# 2_main.net
KiCad netlist of a schematic drawn in EAGLE
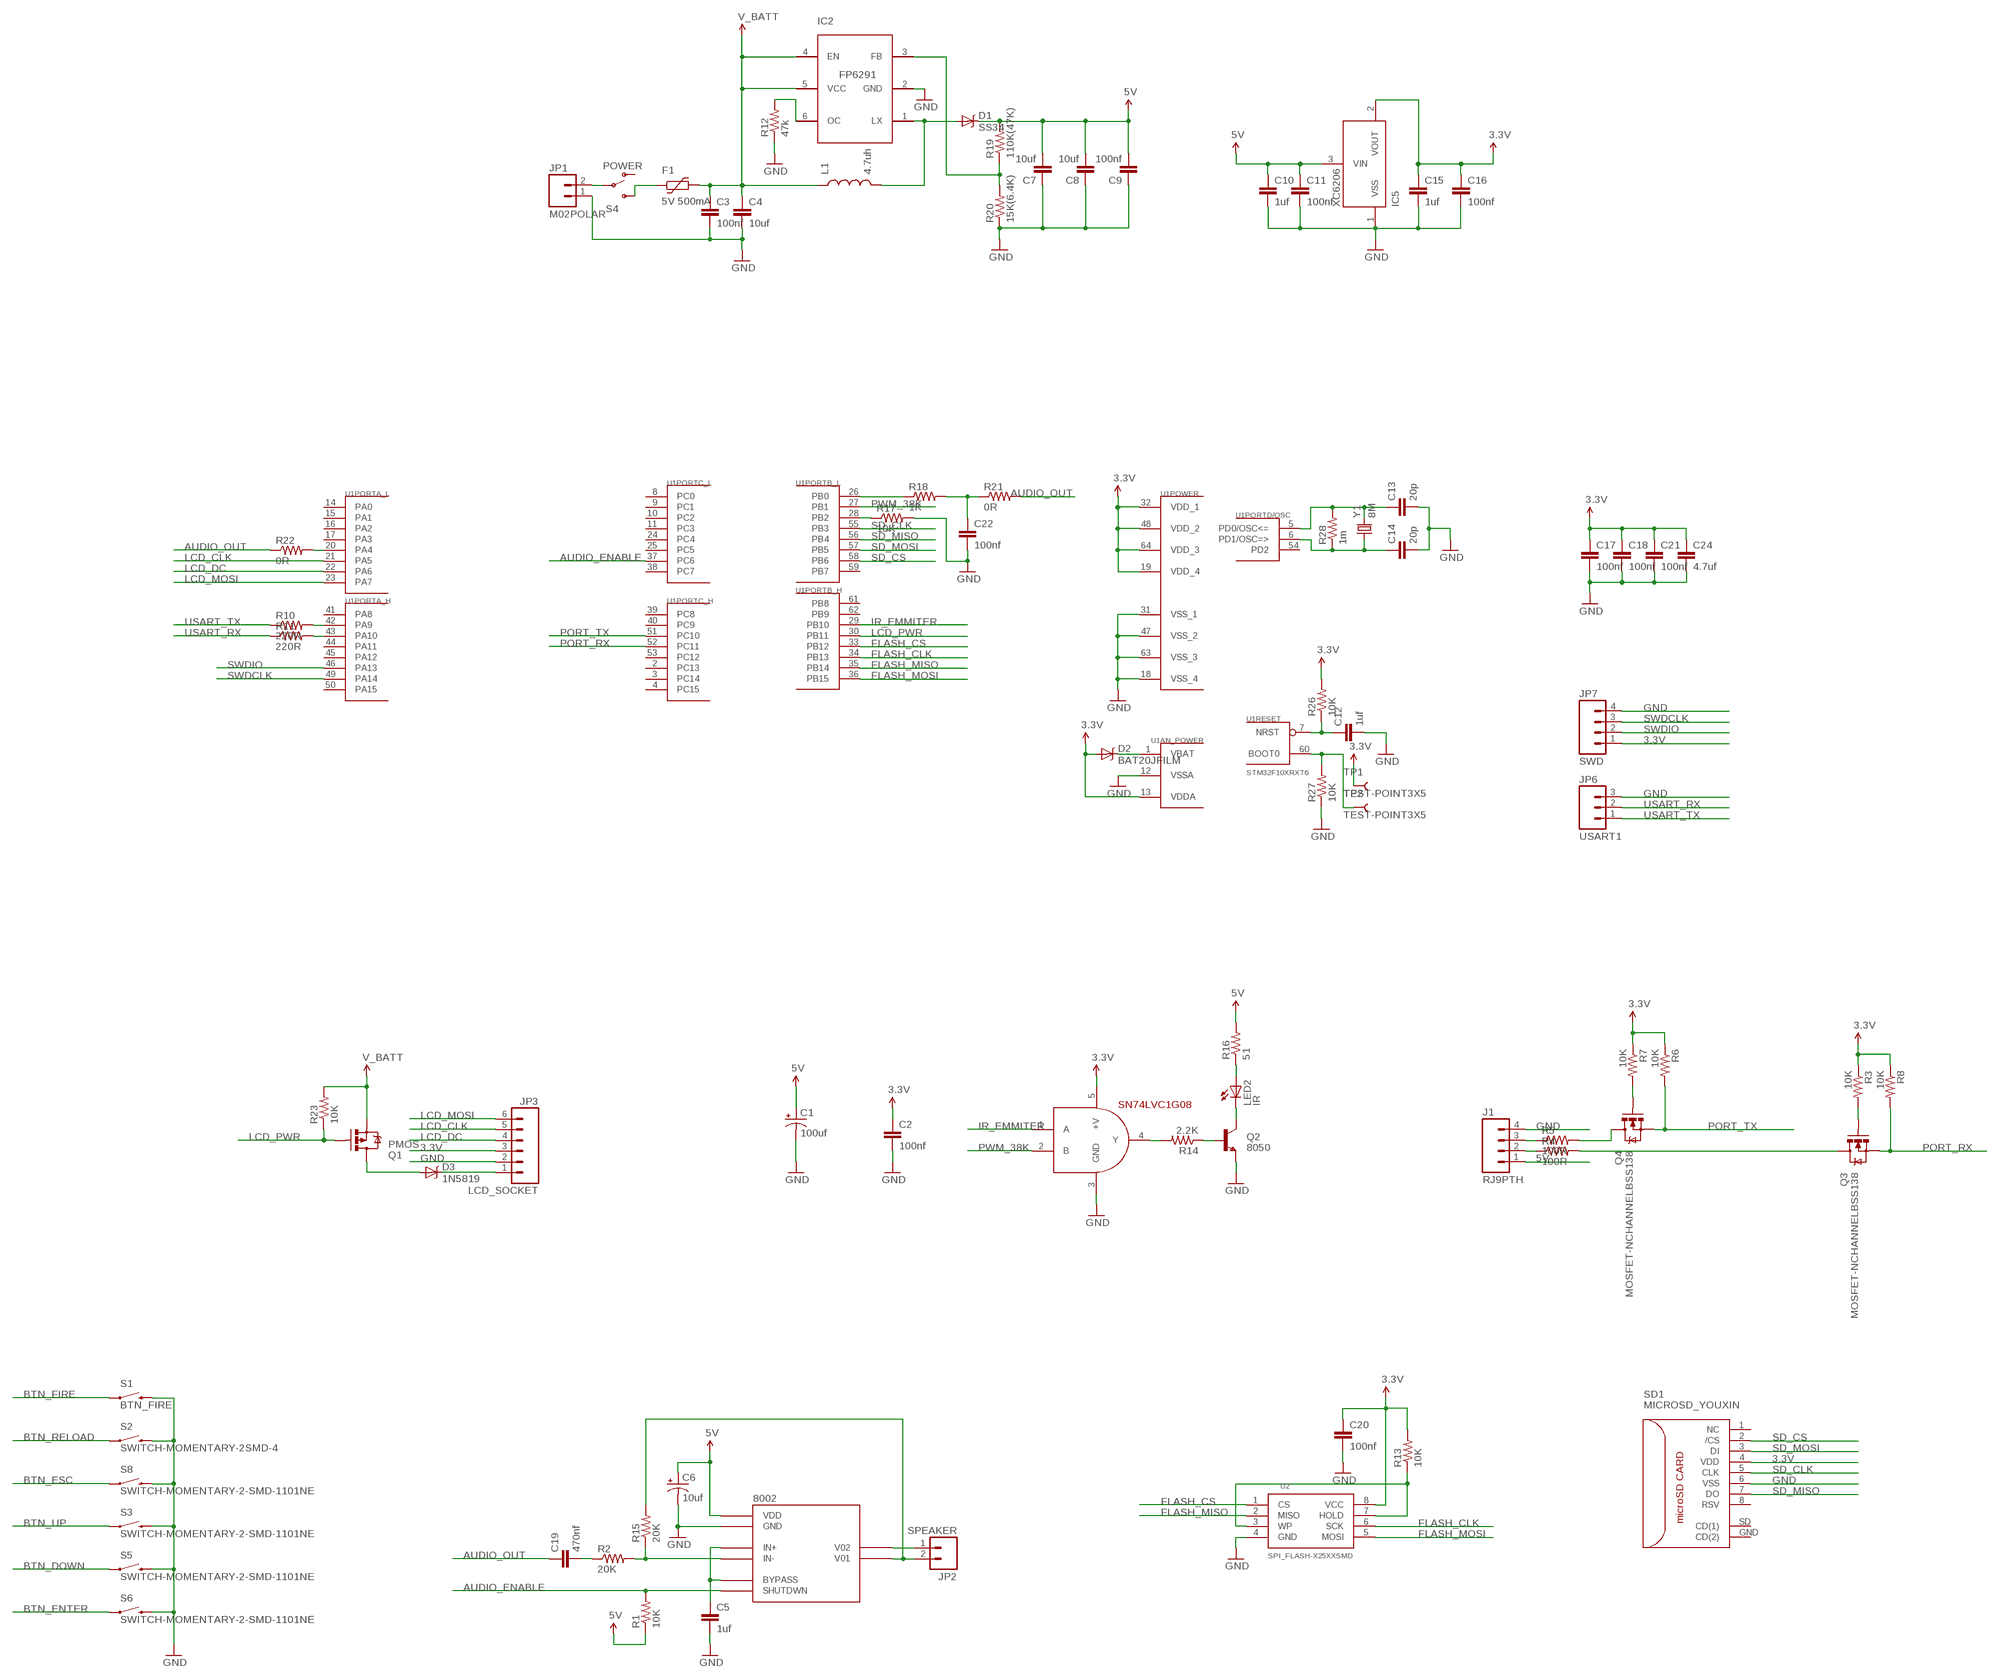
[diagram p0: schematic, sheet 1]

(export (version "E")
  (design (tool "Eeschema 10.0.6"))
  (components
    (comp (ref "8002")
      (value "LM4871")
      (footprint "eagle-import:SO08")
      (libsource (lib "eagle-import") (part "LM4871"))
    )
    (comp (ref "C1")
      (value "100uf")
      (footprint "eagle-import:EIA6032")
      (libsource (lib "eagle-import") (part "CAP_POL6032"))
    )
    (comp (ref "C2")
      (value "100nf")
      (footprint "eagle-import:0603-CAP")
      (libsource (lib "eagle-import") (part "CAP0603-CAP"))
    )
    (comp (ref "C3")
      (value "100nf")
      (footprint "eagle-import:0603-CAP")
      (libsource (lib "eagle-import") (part "CAP0603-CAP"))
    )
    (comp (ref "C4")
      (value "10uf")
      (footprint "eagle-import:0603-CAP")
      (libsource (lib "eagle-import") (part "CAP0603-CAP"))
    )
    (comp (ref "C5")
      (value "1uf")
      (footprint "eagle-import:0603-CAP")
      (libsource (lib "eagle-import") (part "CAP0603-CAP"))
    )
    (comp (ref "C6")
      (value "10uf")
      (footprint "eagle-import:EIA3216-KIT")
      (libsource (lib "eagle-import") (part "CAP_POL1206-KIT"))
    )
    (comp (ref "C7")
      (value "10uf")
      (footprint "eagle-import:0603-CAP")
      (libsource (lib "eagle-import") (part "CAP0603-CAP"))
    )
    (comp (ref "C8")
      (value "10uf")
      (footprint "eagle-import:0603-CAP")
      (libsource (lib "eagle-import") (part "CAP0603-CAP"))
    )
    (comp (ref "C9")
      (value "100nf")
      (footprint "eagle-import:0603-CAP")
      (libsource (lib "eagle-import") (part "CAP0603-CAP"))
    )
    (comp (ref "C10")
      (value "1uf")
      (footprint "eagle-import:0603-CAP")
      (libsource (lib "eagle-import") (part "CAP0603-CAP"))
    )
    (comp (ref "C11")
      (value "100nf")
      (footprint "eagle-import:0603-CAP")
      (libsource (lib "eagle-import") (part "CAP0603-CAP"))
    )
    (comp (ref "C12")
      (value "1uf")
      (footprint "eagle-import:0603-CAP")
      (libsource (lib "eagle-import") (part "CAP0603-CAP"))
    )
    (comp (ref "C13")
      (value "20p")
      (footprint "eagle-import:0603-CAP")
      (libsource (lib "eagle-import") (part "CAP0603-CAP"))
    )
    (comp (ref "C14")
      (value "20p")
      (footprint "eagle-import:0603-CAP")
      (libsource (lib "eagle-import") (part "CAP0603-CAP"))
    )
    (comp (ref "C15")
      (value "1uf")
      (footprint "eagle-import:0603-CAP")
      (libsource (lib "eagle-import") (part "CAP0603-CAP"))
    )
    (comp (ref "C16")
      (value "100nf")
      (footprint "eagle-import:0603-CAP")
      (libsource (lib "eagle-import") (part "CAP0603-CAP"))
    )
    (comp (ref "C17")
      (value "100nf")
      (footprint "eagle-import:0603-CAP")
      (libsource (lib "eagle-import") (part "CAP0603-CAP"))
    )
    (comp (ref "C18")
      (value "100nf")
      (footprint "eagle-import:0603-CAP")
      (libsource (lib "eagle-import") (part "CAP0603-CAP"))
    )
    (comp (ref "C19")
      (value "470nf")
      (footprint "eagle-import:0603-CAP")
      (libsource (lib "eagle-import") (part "CAP0603-CAP"))
    )
    (comp (ref "C20")
      (value "100nf")
      (footprint "eagle-import:0603-CAP")
      (libsource (lib "eagle-import") (part "CAP0603-CAP"))
    )
    (comp (ref "C21")
      (value "100nf")
      (footprint "eagle-import:0603-CAP")
      (libsource (lib "eagle-import") (part "CAP0603-CAP"))
    )
    (comp (ref "C22")
      (value "100nf")
      (footprint "eagle-import:0603-CAP")
      (libsource (lib "eagle-import") (part "CAP0603-CAP"))
    )
    (comp (ref "C24")
      (value "4.7uf")
      (footprint "eagle-import:0603-CAP")
      (libsource (lib "eagle-import") (part "CAP0603-CAP"))
    )
    (comp (ref "D1")
      (value "SS34")
      (footprint "eagle-import:SMA-DIODE")
      (libsource (lib "eagle-import") (part "DIODE-SCHOTTKY_"))
    )
    (comp (ref "D2")
      (value "BAT20JFILM")
      (footprint "eagle-import:SOD-323")
      (libsource (lib "eagle-import") (part "BAT20JFILM"))
    )
    (comp (ref "D3")
      (value "1N5819")
      (footprint "eagle-import:SOD-323")
      (libsource (lib "eagle-import") (part "BAT20JFILM"))
    )
    (comp (ref "F1")
      (value "5V 500mA")
      (footprint "eagle-import:R0805")
      (libsource (lib "eagle-import") (part "PTC-FUSE"))
    )
    (comp (ref "IC1")
      (value "SN74LVC1G08")
      (footprint "eagle-import:SOT23-5")
      (libsource (lib "eagle-import") (part "SN74LVC1G08"))
    )
    (comp (ref "IC2")
      (value "FP6291")
      (footprint "eagle-import:SOT23-6")
      (libsource (lib "eagle-import") (part "FP6291"))
    )
    (comp (ref "IC5")
      (value "XC6206")
      (footprint "eagle-import:SOT23-3")
      (libsource (lib "eagle-import") (part "XC6206"))
    )
    (comp (ref "J1")
      (value "RJ9PTH")
      (footprint "eagle-import:RJ9")
      (libsource (lib "eagle-import") (part "RJ9PTH"))
    )
    (comp (ref "JP1")
      (value "M02POLAR")
      (footprint "eagle-import:MOLEX-1X2")
      (libsource (lib "eagle-import") (part "M02POLAR"))
    )
    (comp (ref "JP2")
      (value "SPEAKER")
      (footprint "eagle-import:MOLEX-1X2")
      (libsource (lib "eagle-import") (part "M02POLAR"))
    )
    (comp (ref "JP3")
      (value "LCD_SOCKET")
      (footprint "eagle-import:MOLEX-1X6")
      (libsource (lib "eagle-import") (part "M06POLAR"))
    )
    (comp (ref "JP6")
      (value "USART1")
      (footprint "eagle-import:1X03")
      (libsource (lib "eagle-import") (part "M03PTH"))
    )
    (comp (ref "JP7")
      (value "SWD")
      (footprint "eagle-import:1X04")
      (libsource (lib "eagle-import") (part "M04PTH"))
    )
    (comp (ref "L1")
      (value "4.7uh")
      (footprint "eagle-import:CR75_V2")
      (libsource (lib "eagle-import") (part "INDUCTORCR75_V2"))
    )
    (comp (ref "LED2")
      (value "IR")
      (footprint "eagle-import:LED5MM")
      (libsource (lib "eagle-import") (part "LED5MM"))
    )
    (comp (ref "Q1")
      (value "PMOS")
      (footprint "eagle-import:SOT23-3")
      (libsource (lib "eagle-import") (part "MOSFET-PCHANNELSMD"))
    )
    (comp (ref "Q2")
      (value "8050")
      (footprint "eagle-import:SOT23")
      (libsource (lib "eagle-import") (part "TRANSISTOR_NPNSOT23"))
    )
    (comp (ref "Q3")
      (value "MOSFET-NCHANNELBSS138")
      (footprint "eagle-import:SOT23")
      (libsource (lib "eagle-import") (part "MOSFET-NCHANNELBSS138"))
    )
    (comp (ref "Q4")
      (value "MOSFET-NCHANNELBSS138")
      (footprint "eagle-import:SOT23")
      (libsource (lib "eagle-import") (part "MOSFET-NCHANNELBSS138"))
    )
    (comp (ref "R1")
      (value "10K")
      (footprint "eagle-import:0603-RES")
      (libsource (lib "eagle-import") (part "RESISTOR0603-RES"))
    )
    (comp (ref "R2")
      (value "20K")
      (footprint "eagle-import:0603-RES")
      (libsource (lib "eagle-import") (part "RESISTOR0603-RES"))
    )
    (comp (ref "R3")
      (value "10K")
      (footprint "eagle-import:0603-RES")
      (libsource (lib "eagle-import") (part "RESISTOR0603-RES"))
    )
    (comp (ref "R4")
      (value "100R")
      (footprint "eagle-import:0603-RES")
      (libsource (lib "eagle-import") (part "RESISTOR0603-RES"))
    )
    (comp (ref "R5")
      (value "100R")
      (footprint "eagle-import:0603-RES")
      (libsource (lib "eagle-import") (part "RESISTOR0603-RES"))
    )
    (comp (ref "R6")
      (value "10K")
      (footprint "eagle-import:0603-RES")
      (libsource (lib "eagle-import") (part "RESISTOR0603-RES"))
    )
    (comp (ref "R7")
      (value "10K")
      (footprint "eagle-import:0603-RES")
      (libsource (lib "eagle-import") (part "RESISTOR0603-RES"))
    )
    (comp (ref "R8")
      (value "10K")
      (footprint "eagle-import:0603-RES")
      (libsource (lib "eagle-import") (part "RESISTOR0603-RES"))
    )
    (comp (ref "R10")
      (value "220R")
      (footprint "eagle-import:0603-RES")
      (libsource (lib "eagle-import") (part "RESISTOR0603-RES"))
    )
    (comp (ref "R11")
      (value "220R")
      (footprint "eagle-import:0603-RES")
      (libsource (lib "eagle-import") (part "RESISTOR0603-RES"))
    )
    (comp (ref "R12")
      (value "47k")
      (footprint "eagle-import:0603-RES")
      (libsource (lib "eagle-import") (part "RESISTOR0603-RES"))
    )
    (comp (ref "R13")
      (value "10K")
      (footprint "eagle-import:0603-RES")
      (libsource (lib "eagle-import") (part "RESISTOR0603-RES"))
    )
    (comp (ref "R14")
      (value "2.2K")
      (footprint "eagle-import:0603-RES")
      (libsource (lib "eagle-import") (part "RESISTOR0603-RES"))
    )
    (comp (ref "R15")
      (value "20K")
      (footprint "eagle-import:0603-RES")
      (libsource (lib "eagle-import") (part "RESISTOR0603-RES"))
    )
    (comp (ref "R16")
      (value "51")
      (footprint "eagle-import:0603-RES")
      (libsource (lib "eagle-import") (part "RESISTOR0603-RES"))
    )
    (comp (ref "R17")
      (value "10K")
      (footprint "eagle-import:0603-RES")
      (libsource (lib "eagle-import") (part "RESISTOR0603-RES"))
    )
    (comp (ref "R18")
      (value "1K")
      (footprint "eagle-import:0603-RES")
      (libsource (lib "eagle-import") (part "RESISTOR0603-RES"))
    )
    (comp (ref "R19")
      (value "110K(47K)")
      (footprint "eagle-import:0603-RES")
      (libsource (lib "eagle-import") (part "RESISTOR0603-RES"))
    )
    (comp (ref "R20")
      (value "15K(6.4K)")
      (footprint "eagle-import:0603-RES")
      (libsource (lib "eagle-import") (part "RESISTOR0603-RES"))
    )
    (comp (ref "R21")
      (value "0R")
      (footprint "eagle-import:0603-RES")
      (libsource (lib "eagle-import") (part "RESISTOR0603-RES"))
    )
    (comp (ref "R22")
      (value "0R")
      (footprint "eagle-import:0603-RES")
      (libsource (lib "eagle-import") (part "RESISTOR0603-RES"))
    )
    (comp (ref "R23")
      (value "10K")
      (footprint "eagle-import:0603-RES")
      (libsource (lib "eagle-import") (part "RESISTOR0603-RES"))
    )
    (comp (ref "R26")
      (value "10K")
      (footprint "eagle-import:0603-RES")
      (libsource (lib "eagle-import") (part "RESISTOR0603-RES"))
    )
    (comp (ref "R27")
      (value "10K")
      (footprint "eagle-import:0603-RES")
      (libsource (lib "eagle-import") (part "RESISTOR0603-RES"))
    )
    (comp (ref "R28")
      (value "1m")
      (footprint "eagle-import:0603-RES")
      (libsource (lib "eagle-import") (part "RESISTOR0603-RES"))
    )
    (comp (ref "S1")
      (value "BTN_FIRE")
      (footprint "eagle-import:TACTILE_SWITCH_TALL")
      (libsource (lib "eagle-import") (part "SWITCH-MOMENTARY-2SMD-4"))
    )
    (comp (ref "S2")
      (value "SWITCH-MOMENTARY-2SMD-4")
      (footprint "eagle-import:TACTILE_SWITCH_TALL")
      (libsource (lib "eagle-import") (part "SWITCH-MOMENTARY-2SMD-4"))
    )
    (comp (ref "S3")
      (value "SWITCH-MOMENTARY-2-SMD-1101NE")
      (footprint "eagle-import:TACTILE-SWITCH-1101NE")
      (libsource (lib "eagle-import") (part "SWITCH-MOMENTARY-2-SMD-1101NE"))
    )
    (comp (ref "S4")
      (value "POWER")
      (footprint "eagle-import:SWITCH-SPDT-AM#6")
      (libsource (lib "eagle-import") (part "SWITCH-SPST3AM6"))
    )
    (comp (ref "S5")
      (value "SWITCH-MOMENTARY-2-SMD-1101NE")
      (footprint "eagle-import:TACTILE-SWITCH-1101NE")
      (libsource (lib "eagle-import") (part "SWITCH-MOMENTARY-2-SMD-1101NE"))
    )
    (comp (ref "S6")
      (value "SWITCH-MOMENTARY-2-SMD-1101NE")
      (footprint "eagle-import:TACTILE-SWITCH-1101NE")
      (libsource (lib "eagle-import") (part "SWITCH-MOMENTARY-2-SMD-1101NE"))
    )
    (comp (ref "S8")
      (value "SWITCH-MOMENTARY-2-SMD-1101NE")
      (footprint "eagle-import:TACTILE-SWITCH-1101NE")
      (libsource (lib "eagle-import") (part "SWITCH-MOMENTARY-2-SMD-1101NE"))
    )
    (comp (ref "SD1")
      (value "MICROSD_YOUXIN")
      (footprint "eagle-import:MICRO_SD_YOUXIN")
      (libsource (lib "eagle-import") (part "MICROSD_YOUXIN"))
    )
    (comp (ref "TP1")
      (value "TEST-POINT3X5")
      (footprint "eagle-import:PAD.03X.05")
      (libsource (lib "eagle-import") (part "TEST-POINT3X5"))
    )
    (comp (ref "TP2")
      (value "TEST-POINT3X5")
      (footprint "eagle-import:PAD.03X.05")
      (libsource (lib "eagle-import") (part "TEST-POINT3X5"))
    )
    (comp (ref "U1")
      (value "STM32F10XRXT6")
      (footprint "eagle-import:TQFP64")
      (libsource (lib "eagle-import") (part "STM32F10XRXT6"))
    )
    (comp (ref "U2")
      (value "SPI_FLASH-X25XXSMD")
      (footprint "eagle-import:SO08")
      (libsource (lib "eagle-import") (part "SPI_FLASH-X25XXSMD"))
    )
    (comp (ref "Y1")
      (value "8M")
      (footprint "eagle-import:CRYSTAL-TXC-7A")
      (libsource (lib "eagle-import") (part "CRYSTALTXC-7A"))
    )
  )
  (nets
    (net (code "1") (name "/AUDIO_ENABLE") (class "Default")
      (node (ref "8002") (pin "1") (pinfunction "SHUTDWN_1") (pintype "bidirectional"))
      (node (ref "R1") (pin "2") (pinfunction "2_2") (pintype "passive"))
      (node (ref "U1") (pin "37") (pinfunction "PC6_37") (pintype "bidirectional"))
    )
    (net (code "2") (name "/AUDIO_OUT") (class "Default")
      (node (ref "C19") (pin "1") (pinfunction "1_1") (pintype "passive"))
      (node (ref "R21") (pin "2") (pinfunction "2_2") (pintype "passive"))
      (node (ref "R22") (pin "1") (pinfunction "1_1") (pintype "passive"))
    )
    (net (code "3") (name "/BTN_DOWN") (class "Default")
      (node (ref "S5") (pin "P$1") (pinfunction "1_P$1") (pintype "passive"))
    )
    (net (code "4") (name "/BTN_ENTER") (class "Default")
      (node (ref "S6") (pin "P$1") (pinfunction "1_P$1") (pintype "passive"))
    )
    (net (code "5") (name "/BTN_ESC") (class "Default")
      (node (ref "S8") (pin "P$1") (pinfunction "1_P$1") (pintype "passive"))
    )
    (net (code "6") (name "/BTN_FIRE") (class "Default")
      (node (ref "S1") (pin "A2") (pinfunction "1_A2") (pintype "passive"))
    )
    (net (code "7") (name "/BTN_RELOAD") (class "Default")
      (node (ref "S2") (pin "A2") (pinfunction "1_A2") (pintype "passive"))
    )
    (net (code "8") (name "/BTN_UP") (class "Default")
      (node (ref "S3") (pin "P$1") (pinfunction "1_P$1") (pintype "passive"))
    )
    (net (code "9") (name "/FLASH_CLK") (class "Default")
      (node (ref "U1") (pin "34") (pinfunction "PB13_34") (pintype "bidirectional"))
      (node (ref "U2") (pin "6") (pinfunction "SCK_6") (pintype "bidirectional"))
    )
    (net (code "10") (name "/FLASH_CS") (class "Default")
      (node (ref "U1") (pin "33") (pinfunction "PB12_33") (pintype "bidirectional"))
      (node (ref "U2") (pin "1") (pinfunction "CS_1") (pintype "bidirectional"))
    )
    (net (code "11") (name "/FLASH_MISO") (class "Default")
      (node (ref "U1") (pin "35") (pinfunction "PB14_35") (pintype "bidirectional"))
      (node (ref "U2") (pin "2") (pinfunction "MISO_2") (pintype "bidirectional"))
    )
    (net (code "12") (name "/FLASH_MOSI") (class "Default")
      (node (ref "U1") (pin "36") (pinfunction "PB15_36") (pintype "bidirectional"))
      (node (ref "U2") (pin "5") (pinfunction "MOSI_5") (pintype "bidirectional"))
    )
    (net (code "13") (name "/IR_EMMITER") (class "Default")
      (node (ref "IC1") (pin "1") (pinfunction "A_1") (pintype "bidirectional"))
      (node (ref "U1") (pin "29") (pinfunction "PB10_29") (pintype "bidirectional"))
    )
    (net (code "14") (name "/LCD_CLK") (class "Default")
      (node (ref "JP3") (pin "5") (pinfunction "5_5") (pintype "passive"))
      (node (ref "U1") (pin "21") (pinfunction "PA5_21") (pintype "bidirectional"))
    )
    (net (code "15") (name "/LCD_DC") (class "Default")
      (node (ref "JP3") (pin "4") (pinfunction "4_4") (pintype "passive"))
      (node (ref "U1") (pin "22") (pinfunction "PA6_22") (pintype "bidirectional"))
    )
    (net (code "16") (name "/LCD_MOSI") (class "Default")
      (node (ref "JP3") (pin "6") (pinfunction "6_6") (pintype "passive"))
      (node (ref "U1") (pin "23") (pinfunction "PA7_23") (pintype "bidirectional"))
    )
    (net (code "17") (name "/LCD_PWR") (class "Default")
      (node (ref "Q1") (pin "1") (pinfunction "G_1") (pintype "passive"))
      (node (ref "R23") (pin "1") (pinfunction "1_1") (pintype "passive"))
      (node (ref "U1") (pin "30") (pinfunction "PB11_30") (pintype "bidirectional"))
    )
    (net (code "18") (name "/PORT_RX") (class "Default")
      (node (ref "Q3") (pin "2") (pinfunction "S_2") (pintype "passive"))
      (node (ref "R8") (pin "2") (pinfunction "2_2") (pintype "passive"))
      (node (ref "U1") (pin "52") (pinfunction "PC11_52") (pintype "bidirectional"))
    )
    (net (code "19") (name "/PORT_TX") (class "Default")
      (node (ref "Q4") (pin "2") (pinfunction "S_2") (pintype "passive"))
      (node (ref "R6") (pin "2") (pinfunction "2_2") (pintype "passive"))
      (node (ref "U1") (pin "51") (pinfunction "PC10_51") (pintype "bidirectional"))
    )
    (net (code "20") (name "/PWM_38K") (class "Default")
      (node (ref "IC1") (pin "2") (pinfunction "B_2") (pintype "bidirectional"))
      (node (ref "U1") (pin "27") (pinfunction "PB1_27") (pintype "bidirectional"))
    )
    (net (code "21") (name "/SD_CLK") (class "Default")
      (node (ref "SD1") (pin "5") (pinfunction "CLK_5") (pintype "bidirectional"))
      (node (ref "U1") (pin "55") (pinfunction "PB3_55") (pintype "bidirectional"))
    )
    (net (code "22") (name "/SD_CS") (class "Default")
      (node (ref "SD1") (pin "2") (pinfunction "/CS_2") (pintype "bidirectional"))
      (node (ref "U1") (pin "58") (pinfunction "PB6_58") (pintype "bidirectional"))
    )
    (net (code "23") (name "/SD_MISO") (class "Default")
      (node (ref "SD1") (pin "7") (pinfunction "DO_7") (pintype "bidirectional"))
      (node (ref "U1") (pin "56") (pinfunction "PB4_56") (pintype "bidirectional"))
    )
    (net (code "24") (name "/SD_MOSI") (class "Default")
      (node (ref "SD1") (pin "3") (pinfunction "DI_3") (pintype "bidirectional"))
      (node (ref "U1") (pin "57") (pinfunction "PB5_57") (pintype "bidirectional"))
    )
    (net (code "25") (name "/SWDCLK") (class "Default")
      (node (ref "JP7") (pin "3") (pinfunction "3_3") (pintype "passive"))
      (node (ref "U1") (pin "49") (pinfunction "PA14_49") (pintype "bidirectional"))
    )
    (net (code "26") (name "/SWDIO") (class "Default")
      (node (ref "JP7") (pin "2") (pinfunction "2_2") (pintype "passive"))
      (node (ref "U1") (pin "46") (pinfunction "PA13_46") (pintype "bidirectional"))
    )
    (net (code "27") (name "/USART_RX") (class "Default")
      (node (ref "JP6") (pin "2") (pinfunction "2_2") (pintype "passive"))
      (node (ref "R11") (pin "1") (pinfunction "1_1") (pintype "passive"))
    )
    (net (code "28") (name "/USART_TX") (class "Default")
      (node (ref "JP6") (pin "1") (pinfunction "1_1") (pintype "passive"))
      (node (ref "R10") (pin "1") (pinfunction "1_1") (pintype "passive"))
    )
    (net (code "29") (name "3.3V") (class "Default")
      (node (ref "C15") (pin "1") (pinfunction "1_1") (pintype "passive"))
      (node (ref "C16") (pin "1") (pinfunction "1_1") (pintype "passive"))
      (node (ref "C17") (pin "1") (pinfunction "1_1") (pintype "passive"))
      (node (ref "C18") (pin "1") (pinfunction "1_1") (pintype "passive"))
      (node (ref "C2") (pin "1") (pinfunction "1_1") (pintype "passive"))
      (node (ref "C20") (pin "1") (pinfunction "1_1") (pintype "passive"))
      (node (ref "C21") (pin "1") (pinfunction "1_1") (pintype "passive"))
      (node (ref "C24") (pin "1") (pinfunction "1_1") (pintype "passive"))
      (node (ref "D2") (pin "2") (pinfunction "A_2") (pintype "passive"))
      (node (ref "IC1") (pin "5") (pinfunction "+V_5") (pintype "bidirectional"))
      (node (ref "IC5") (pin "2") (pinfunction "VOUT_2") (pintype "power_in"))
      (node (ref "JP3") (pin "3") (pinfunction "3_3") (pintype "passive"))
      (node (ref "JP7") (pin "1") (pinfunction "1_1") (pintype "passive"))
      (node (ref "R13") (pin "2") (pinfunction "2_2") (pintype "passive"))
      (node (ref "R26") (pin "2") (pinfunction "2_2") (pintype "passive"))
      (node (ref "R3") (pin "1") (pinfunction "1_1") (pintype "passive"))
      (node (ref "R6") (pin "1") (pinfunction "1_1") (pintype "passive"))
      (node (ref "R7") (pin "1") (pinfunction "1_1") (pintype "passive"))
      (node (ref "R8") (pin "1") (pinfunction "1_1") (pintype "passive"))
      (node (ref "SD1") (pin "4") (pinfunction "VDD_4") (pintype "bidirectional"))
      (node (ref "TP1") (pin "P$1") (pinfunction "1_P$1") (pintype "bidirectional"))
      (node (ref "U1") (pin "13") (pinfunction "VDDA_13") (pintype "power_in"))
      (node (ref "U1") (pin "19") (pinfunction "VDD_4_19") (pintype "power_in"))
      (node (ref "U1") (pin "32") (pinfunction "VDD_1_32") (pintype "power_in"))
      (node (ref "U1") (pin "48") (pinfunction "VDD_2_48") (pintype "power_in"))
      (node (ref "U1") (pin "64") (pinfunction "VDD_3_64") (pintype "power_in"))
      (node (ref "U2") (pin "8") (pinfunction "VCC_8") (pintype "bidirectional"))
    )
    (net (code "30") (name "5V") (class "Default")
      (node (ref "8002") (pin "6") (pinfunction "VDD_6") (pintype "bidirectional"))
      (node (ref "C1") (pin "P$1") (pinfunction "+_P$1") (pintype "passive"))
      (node (ref "C10") (pin "1") (pinfunction "1_1") (pintype "passive"))
      (node (ref "C11") (pin "1") (pinfunction "1_1") (pintype "passive"))
      (node (ref "C6") (pin "A") (pinfunction "+_A") (pintype "passive"))
      (node (ref "C7") (pin "2") (pinfunction "2_2") (pintype "passive"))
      (node (ref "C8") (pin "2") (pinfunction "2_2") (pintype "passive"))
      (node (ref "C9") (pin "2") (pinfunction "2_2") (pintype "passive"))
      (node (ref "D1") (pin "C") (pinfunction "C_C") (pintype "passive"))
      (node (ref "IC5") (pin "3") (pinfunction "VIN_3") (pintype "power_in"))
      (node (ref "J1") (pin "1") (pinfunction "1_1") (pintype "passive"))
      (node (ref "R1") (pin "1") (pinfunction "1_1") (pintype "passive"))
      (node (ref "R16") (pin "2") (pinfunction "2_2") (pintype "passive"))
      (node (ref "R19") (pin "2") (pinfunction "2_2") (pintype "passive"))
    )
    (net (code "31") (name "GND") (class "Default")
      (node (ref "8002") (pin "7") (pinfunction "GND_7") (pintype "bidirectional"))
      (node (ref "C1") (pin "P$2") (pinfunction "-_P$2") (pintype "passive"))
      (node (ref "C10") (pin "2") (pinfunction "2_2") (pintype "passive"))
      (node (ref "C11") (pin "2") (pinfunction "2_2") (pintype "passive"))
      (node (ref "C12") (pin "2") (pinfunction "2_2") (pintype "passive"))
      (node (ref "C13") (pin "2") (pinfunction "2_2") (pintype "passive"))
      (node (ref "C14") (pin "2") (pinfunction "2_2") (pintype "passive"))
      (node (ref "C15") (pin "2") (pinfunction "2_2") (pintype "passive"))
      (node (ref "C16") (pin "2") (pinfunction "2_2") (pintype "passive"))
      (node (ref "C17") (pin "2") (pinfunction "2_2") (pintype "passive"))
      (node (ref "C18") (pin "2") (pinfunction "2_2") (pintype "passive"))
      (node (ref "C2") (pin "2") (pinfunction "2_2") (pintype "passive"))
      (node (ref "C20") (pin "2") (pinfunction "2_2") (pintype "passive"))
      (node (ref "C21") (pin "2") (pinfunction "2_2") (pintype "passive"))
      (node (ref "C22") (pin "2") (pinfunction "2_2") (pintype "passive"))
      (node (ref "C24") (pin "2") (pinfunction "2_2") (pintype "passive"))
      (node (ref "C3") (pin "2") (pinfunction "2_2") (pintype "passive"))
      (node (ref "C4") (pin "2") (pinfunction "2_2") (pintype "passive"))
      (node (ref "C5") (pin "2") (pinfunction "2_2") (pintype "passive"))
      (node (ref "C6") (pin "C") (pinfunction "-_C") (pintype "passive"))
      (node (ref "C7") (pin "1") (pinfunction "1_1") (pintype "passive"))
      (node (ref "C8") (pin "1") (pinfunction "1_1") (pintype "passive"))
      (node (ref "C9") (pin "1") (pinfunction "1_1") (pintype "passive"))
      (node (ref "IC1") (pin "3") (pinfunction "GND_3") (pintype "bidirectional"))
      (node (ref "IC2") (pin "2") (pinfunction "GND_2") (pintype "power_in"))
      (node (ref "IC5") (pin "1") (pinfunction "VSS_1") (pintype "power_in"))
      (node (ref "J1") (pin "4") (pinfunction "4_4") (pintype "passive"))
      (node (ref "JP1") (pin "1") (pinfunction "1_1") (pintype "passive"))
      (node (ref "JP3") (pin "2") (pinfunction "2_2") (pintype "passive"))
      (node (ref "JP6") (pin "3") (pinfunction "3_3") (pintype "passive"))
      (node (ref "JP7") (pin "4") (pinfunction "4_4") (pintype "passive"))
      (node (ref "Q2") (pin "2") (pinfunction "E_2") (pintype "passive"))
      (node (ref "R12") (pin "1") (pinfunction "1_1") (pintype "passive"))
      (node (ref "R17") (pin "2") (pinfunction "2_2") (pintype "passive"))
      (node (ref "R20") (pin "1") (pinfunction "1_1") (pintype "passive"))
      (node (ref "R27") (pin "1") (pinfunction "1_1") (pintype "passive"))
      (node (ref "S1") (pin "B2") (pinfunction "2_B2") (pintype "passive"))
      (node (ref "S2") (pin "B2") (pinfunction "2_B2") (pintype "passive"))
      (node (ref "S3") (pin "P$2") (pinfunction "2_P$2") (pintype "passive"))
      (node (ref "S5") (pin "P$2") (pinfunction "2_P$2") (pintype "passive"))
      (node (ref "S6") (pin "P$2") (pinfunction "2_P$2") (pintype "passive"))
      (node (ref "S8") (pin "P$2") (pinfunction "2_P$2") (pintype "passive"))
      (node (ref "SD1") (pin "6") (pinfunction "VSS_6") (pintype "bidirectional"))
      (node (ref "U1") (pin "12") (pinfunction "VSSA_12") (pintype "power_in"))
      (node (ref "U1") (pin "18") (pinfunction "VSS_4_18") (pintype "power_in"))
      (node (ref "U1") (pin "31") (pinfunction "VSS_1_31") (pintype "power_in"))
      (node (ref "U1") (pin "47") (pinfunction "VSS_2_47") (pintype "power_in"))
      (node (ref "U1") (pin "63") (pinfunction "VSS_3_63") (pintype "power_in"))
      (node (ref "U2") (pin "4") (pinfunction "GND_4") (pintype "bidirectional"))
    )
    (net (code "32") (name "Net-(8002-BYPASS)") (class "Default")
      (node (ref "8002") (pin "2") (pinfunction "BYPASS_2") (pintype "bidirectional"))
      (node (ref "8002") (pin "3") (pinfunction "IN+_3") (pintype "bidirectional"))
      (node (ref "C5") (pin "1") (pinfunction "1_1") (pintype "passive"))
    )
    (net (code "33") (name "Net-(8002-IN-)") (class "Default")
      (node (ref "8002") (pin "4") (pinfunction "IN-_4") (pintype "bidirectional"))
      (node (ref "R15") (pin "1") (pinfunction "1_1") (pintype "passive"))
      (node (ref "R2") (pin "2") (pinfunction "2_2") (pintype "passive"))
    )
    (net (code "34") (name "Net-(8002-V01)") (class "Default")
      (node (ref "8002") (pin "5") (pinfunction "V01_5") (pintype "bidirectional"))
      (node (ref "JP2") (pin "2") (pinfunction "2_2") (pintype "passive"))
      (node (ref "R15") (pin "2") (pinfunction "2_2") (pintype "passive"))
    )
    (net (code "35") (name "Net-(8002-V02)") (class "Default")
      (node (ref "8002") (pin "8") (pinfunction "V02_8") (pintype "bidirectional"))
      (node (ref "JP2") (pin "1") (pinfunction "1_1") (pintype "passive"))
    )
    (net (code "36") (name "Net-(C19-Pad2)") (class "Default")
      (node (ref "C19") (pin "2") (pinfunction "2_2") (pintype "passive"))
      (node (ref "R2") (pin "1") (pinfunction "1_1") (pintype "passive"))
    )
    (net (code "37") (name "Net-(C22-Pad1)") (class "Default")
      (node (ref "C22") (pin "1") (pinfunction "1_1") (pintype "passive"))
      (node (ref "R18") (pin "2") (pinfunction "2_2") (pintype "passive"))
      (node (ref "R21") (pin "1") (pinfunction "1_1") (pintype "passive"))
    )
    (net (code "38") (name "Net-(D2-C)") (class "Default")
      (node (ref "D2") (pin "1") (pinfunction "C_1") (pintype "passive"))
      (node (ref "U1") (pin "1") (pinfunction "VBAT_1") (pintype "power_in"))
    )
    (net (code "39") (name "Net-(D3-A)") (class "Default")
      (node (ref "D3") (pin "2") (pinfunction "A_2") (pintype "passive"))
      (node (ref "Q1") (pin "3") (pinfunction "D_3") (pintype "passive"))
    )
    (net (code "40") (name "Net-(D3-C)") (class "Default")
      (node (ref "D3") (pin "1") (pinfunction "C_1") (pintype "passive"))
      (node (ref "JP3") (pin "1") (pinfunction "1_1") (pintype "passive"))
    )
    (net (code "41") (name "Net-(IC1-Y)") (class "Default")
      (node (ref "IC1") (pin "4") (pinfunction "Y_4") (pintype "bidirectional"))
      (node (ref "R14") (pin "2") (pinfunction "2_2") (pintype "passive"))
    )
    (net (code "42") (name "Net-(IC2-FB)") (class "Default")
      (node (ref "IC2") (pin "3") (pinfunction "FB_3") (pintype "bidirectional"))
      (node (ref "R19") (pin "1") (pinfunction "1_1") (pintype "passive"))
      (node (ref "R20") (pin "2") (pinfunction "2_2") (pintype "passive"))
    )
    (net (code "43") (name "Net-(IC2-LX)") (class "Default")
      (node (ref "D1") (pin "A") (pinfunction "A_A") (pintype "passive"))
      (node (ref "IC2") (pin "1") (pinfunction "LX_1") (pintype "bidirectional"))
      (node (ref "L1") (pin "P$2") (pinfunction "2_P$2") (pintype "passive"))
    )
    (net (code "44") (name "Net-(IC2-OC)") (class "Default")
      (node (ref "IC2") (pin "6") (pinfunction "OC_6") (pintype "open_collector"))
      (node (ref "R12") (pin "2") (pinfunction "2_2") (pintype "passive"))
    )
    (net (code "45") (name "Net-(J1-Pad2)") (class "Default")
      (node (ref "J1") (pin "2") (pinfunction "2_2") (pintype "passive"))
      (node (ref "R4") (pin "1") (pinfunction "1_1") (pintype "passive"))
    )
    (net (code "46") (name "Net-(J1-Pad3)") (class "Default")
      (node (ref "J1") (pin "3") (pinfunction "3_3") (pintype "passive"))
      (node (ref "R5") (pin "1") (pinfunction "1_1") (pintype "passive"))
    )
    (net (code "47") (name "Net-(LED2-C)") (class "Default")
      (node (ref "LED2") (pin "K") (pinfunction "C_K") (pintype "passive"))
      (node (ref "Q2") (pin "3") (pinfunction "C_3") (pintype "passive"))
    )
    (net (code "48") (name "Net-(LED2-PadA)") (class "Default")
      (node (ref "LED2") (pin "A") (pinfunction "A_A") (pintype "passive"))
      (node (ref "R16") (pin "1") (pinfunction "1_1") (pintype "passive"))
    )
    (net (code "49") (name "Net-(Q2-B)") (class "Default")
      (node (ref "Q2") (pin "1") (pinfunction "B_1") (pintype "passive"))
      (node (ref "R14") (pin "1") (pinfunction "1_1") (pintype "passive"))
    )
    (net (code "50") (name "Net-(Q3-D)") (class "Default")
      (node (ref "Q3") (pin "3") (pinfunction "D_3") (pintype "passive"))
      (node (ref "R4") (pin "2") (pinfunction "2_2") (pintype "passive"))
    )
    (net (code "51") (name "Net-(Q3-G)") (class "Default")
      (node (ref "Q3") (pin "1") (pinfunction "G_1") (pintype "passive"))
      (node (ref "R3") (pin "2") (pinfunction "2_2") (pintype "passive"))
    )
    (net (code "52") (name "Net-(Q4-D)") (class "Default")
      (node (ref "Q4") (pin "3") (pinfunction "D_3") (pintype "passive"))
      (node (ref "R5") (pin "2") (pinfunction "2_2") (pintype "passive"))
    )
    (net (code "53") (name "Net-(Q4-G)") (class "Default")
      (node (ref "Q4") (pin "1") (pinfunction "G_1") (pintype "passive"))
      (node (ref "R7") (pin "2") (pinfunction "2_2") (pintype "passive"))
    )
    (net (code "54") (name "Net-(S4-P)") (class "Default")
      (node (ref "JP1") (pin "2") (pinfunction "2_2") (pintype "passive"))
      (node (ref "S4") (pin "2") (pinfunction "P_2") (pintype "passive"))
    )
    (net (code "55") (name "Net-(S4-S)") (class "Default")
      (node (ref "F1") (pin "1") (pinfunction "1_1") (pintype "passive"))
      (node (ref "S4") (pin "3") (pinfunction "S_3") (pintype "passive"))
    )
    (net (code "56") (name "Net-(TP2-1)") (class "Default")
      (node (ref "R27") (pin "2") (pinfunction "2_2") (pintype "passive"))
      (node (ref "TP2") (pin "P$1") (pinfunction "1_P$1") (pintype "bidirectional"))
      (node (ref "U1") (pin "60") (pinfunction "BOOT0_60") (pintype "input"))
    )
    (net (code "57") (name "Net-(U1B-PA9)") (class "Default")
      (node (ref "R10") (pin "2") (pinfunction "2_2") (pintype "passive"))
      (node (ref "U1") (pin "42") (pinfunction "PA9_42") (pintype "bidirectional"))
    )
    (net (code "58") (name "Net-(U1B-PA10)") (class "Default")
      (node (ref "R11") (pin "2") (pinfunction "2_2") (pintype "passive"))
      (node (ref "U1") (pin "43") (pinfunction "PA10_43") (pintype "bidirectional"))
    )
    (net (code "59") (name "Net-(U1C-PA4)") (class "Default")
      (node (ref "R22") (pin "2") (pinfunction "2_2") (pintype "passive"))
      (node (ref "U1") (pin "20") (pinfunction "PA4_20") (pintype "bidirectional"))
    )
    (net (code "60") (name "Net-(U1E-PB0)") (class "Default")
      (node (ref "R18") (pin "1") (pinfunction "1_1") (pintype "passive"))
      (node (ref "U1") (pin "26") (pinfunction "PB0_26") (pintype "bidirectional"))
    )
    (net (code "61") (name "Net-(U1E-PB2)") (class "Default")
      (node (ref "R17") (pin "1") (pinfunction "1_1") (pintype "passive"))
      (node (ref "U1") (pin "28") (pinfunction "PB2_28") (pintype "bidirectional"))
    )
    (net (code "62") (name "Net-(U1H-PD0{slash}OSC<=)") (class "Default")
      (node (ref "C13") (pin "1") (pinfunction "1_1") (pintype "passive"))
      (node (ref "R28") (pin "2") (pinfunction "2_2") (pintype "passive"))
      (node (ref "U1") (pin "5") (pinfunction "PD0/OSC<=_5") (pintype "bidirectional"))
      (node (ref "Y1") (pin "P$2") (pinfunction "2_P$2") (pintype "passive"))
    )
    (net (code "63") (name "Net-(U1H-PD1{slash}OSC=>)") (class "Default")
      (node (ref "C14") (pin "1") (pinfunction "1_1") (pintype "passive"))
      (node (ref "R28") (pin "1") (pinfunction "1_1") (pintype "passive"))
      (node (ref "U1") (pin "6") (pinfunction "PD1/OSC=>_6") (pintype "bidirectional"))
      (node (ref "Y1") (pin "P$1") (pinfunction "1_P$1") (pintype "passive"))
    )
    (net (code "64") (name "Net-(U1J-NRST)") (class "Default")
      (node (ref "C12") (pin "1") (pinfunction "1_1") (pintype "passive"))
      (node (ref "R26") (pin "1") (pinfunction "1_1") (pintype "passive"))
      (node (ref "U1") (pin "7") (pinfunction "NRST_7") (pintype "input"))
    )
    (net (code "65") (name "Net-(U2-HOLD)") (class "Default")
      (node (ref "R13") (pin "1") (pinfunction "1_1") (pintype "passive"))
      (node (ref "U2") (pin "3") (pinfunction "WP_3") (pintype "bidirectional"))
      (node (ref "U2") (pin "7") (pinfunction "HOLD_7") (pintype "bidirectional"))
    )
    (net (code "66") (name "V_BATT") (class "Default")
      (node (ref "C3") (pin "1") (pinfunction "1_1") (pintype "passive"))
      (node (ref "C4") (pin "1") (pinfunction "1_1") (pintype "passive"))
      (node (ref "F1") (pin "2") (pinfunction "2_2") (pintype "passive"))
      (node (ref "IC2") (pin "4") (pinfunction "EN_4") (pintype "bidirectional"))
      (node (ref "IC2") (pin "5") (pinfunction "VCC_5") (pintype "power_in"))
      (node (ref "L1") (pin "P$1") (pinfunction "1_P$1") (pintype "passive"))
      (node (ref "Q1") (pin "2") (pinfunction "S_2") (pintype "passive"))
      (node (ref "R23") (pin "2") (pinfunction "2_2") (pintype "passive"))
    )
    (net (code "67") (name "unconnected-(S4-O-Pad1)") (class "Default")
      (node (ref "S4") (pin "1") (pinfunction "O_1") (pintype "passive"))
    )
    (net (code "68") (name "unconnected-(SD1-CD(1)-PadSD)") (class "Default")
      (node (ref "SD1") (pin "SD") (pinfunction "CD(1)_SD") (pintype "bidirectional"))
    )
    (net (code "69") (name "unconnected-(SD1-CD(2)-PadGND)") (class "Default")
      (node (ref "SD1") (pin "GND") (pinfunction "CD(2)_GND") (pintype "bidirectional"))
    )
    (net (code "70") (name "unconnected-(SD1-NC-Pad1)") (class "Default")
      (node (ref "SD1") (pin "1") (pinfunction "NC_1") (pintype "bidirectional"))
    )
    (net (code "71") (name "unconnected-(SD1-RSV-Pad8)") (class "Default")
      (node (ref "SD1") (pin "8") (pinfunction "RSV_8") (pintype "bidirectional"))
    )
    (net (code "72") (name "unconnected-(U1B-PA8-Pad41)") (class "Default")
      (node (ref "U1") (pin "41") (pinfunction "PA8_41") (pintype "bidirectional"))
    )
    (net (code "73") (name "unconnected-(U1B-PA11-Pad44)") (class "Default")
      (node (ref "U1") (pin "44") (pinfunction "PA11_44") (pintype "bidirectional"))
    )
    (net (code "74") (name "unconnected-(U1B-PA12-Pad45)") (class "Default")
      (node (ref "U1") (pin "45") (pinfunction "PA12_45") (pintype "bidirectional"))
    )
    (net (code "75") (name "unconnected-(U1B-PA15-Pad50)") (class "Default")
      (node (ref "U1") (pin "50") (pinfunction "PA15_50") (pintype "bidirectional"))
    )
    (net (code "76") (name "unconnected-(U1C-PA0-Pad14)") (class "Default")
      (node (ref "U1") (pin "14") (pinfunction "PA0_14") (pintype "bidirectional"))
    )
    (net (code "77") (name "unconnected-(U1C-PA1-Pad15)") (class "Default")
      (node (ref "U1") (pin "15") (pinfunction "PA1_15") (pintype "bidirectional"))
    )
    (net (code "78") (name "unconnected-(U1C-PA2-Pad16)") (class "Default")
      (node (ref "U1") (pin "16") (pinfunction "PA2_16") (pintype "bidirectional"))
    )
    (net (code "79") (name "unconnected-(U1C-PA3-Pad17)") (class "Default")
      (node (ref "U1") (pin "17") (pinfunction "PA3_17") (pintype "bidirectional"))
    )
    (net (code "80") (name "unconnected-(U1D-PB8-Pad61)") (class "Default")
      (node (ref "U1") (pin "61") (pinfunction "PB8_61") (pintype "bidirectional"))
    )
    (net (code "81") (name "unconnected-(U1D-PB9-Pad62)") (class "Default")
      (node (ref "U1") (pin "62") (pinfunction "PB9_62") (pintype "bidirectional"))
    )
    (net (code "82") (name "unconnected-(U1E-PB7-Pad59)") (class "Default")
      (node (ref "U1") (pin "59") (pinfunction "PB7_59") (pintype "bidirectional"))
    )
    (net (code "83") (name "unconnected-(U1F-PC8-Pad39)") (class "Default")
      (node (ref "U1") (pin "39") (pinfunction "PC8_39") (pintype "bidirectional"))
    )
    (net (code "84") (name "unconnected-(U1F-PC9-Pad40)") (class "Default")
      (node (ref "U1") (pin "40") (pinfunction "PC9_40") (pintype "bidirectional"))
    )
    (net (code "85") (name "unconnected-(U1F-PC12-Pad53)") (class "Default")
      (node (ref "U1") (pin "53") (pinfunction "PC12_53") (pintype "bidirectional"))
    )
    (net (code "86") (name "unconnected-(U1F-PC13-Pad2)") (class "Default")
      (node (ref "U1") (pin "2") (pinfunction "PC13_2") (pintype "bidirectional"))
    )
    (net (code "87") (name "unconnected-(U1F-PC14-Pad3)") (class "Default")
      (node (ref "U1") (pin "3") (pinfunction "PC14_3") (pintype "bidirectional"))
    )
    (net (code "88") (name "unconnected-(U1F-PC15-Pad4)") (class "Default")
      (node (ref "U1") (pin "4") (pinfunction "PC15_4") (pintype "bidirectional"))
    )
    (net (code "89") (name "unconnected-(U1G-PC0-Pad8)") (class "Default")
      (node (ref "U1") (pin "8") (pinfunction "PC0_8") (pintype "bidirectional"))
    )
    (net (code "90") (name "unconnected-(U1G-PC1-Pad9)") (class "Default")
      (node (ref "U1") (pin "9") (pinfunction "PC1_9") (pintype "bidirectional"))
    )
    (net (code "91") (name "unconnected-(U1G-PC2-Pad10)") (class "Default")
      (node (ref "U1") (pin "10") (pinfunction "PC2_10") (pintype "bidirectional"))
    )
    (net (code "92") (name "unconnected-(U1G-PC3-Pad11)") (class "Default")
      (node (ref "U1") (pin "11") (pinfunction "PC3_11") (pintype "bidirectional"))
    )
    (net (code "93") (name "unconnected-(U1G-PC4-Pad24)") (class "Default")
      (node (ref "U1") (pin "24") (pinfunction "PC4_24") (pintype "bidirectional"))
    )
    (net (code "94") (name "unconnected-(U1G-PC5-Pad25)") (class "Default")
      (node (ref "U1") (pin "25") (pinfunction "PC5_25") (pintype "bidirectional"))
    )
    (net (code "95") (name "unconnected-(U1G-PC7-Pad38)") (class "Default")
      (node (ref "U1") (pin "38") (pinfunction "PC7_38") (pintype "bidirectional"))
    )
    (net (code "96") (name "unconnected-(U1H-PD2-Pad54)") (class "Default")
      (node (ref "U1") (pin "54") (pinfunction "PD2_54") (pintype "bidirectional"))
    )
  )
)
